# Smart_Restaurant.net
KiCad netlist of a schematic drawn in Altium Designer
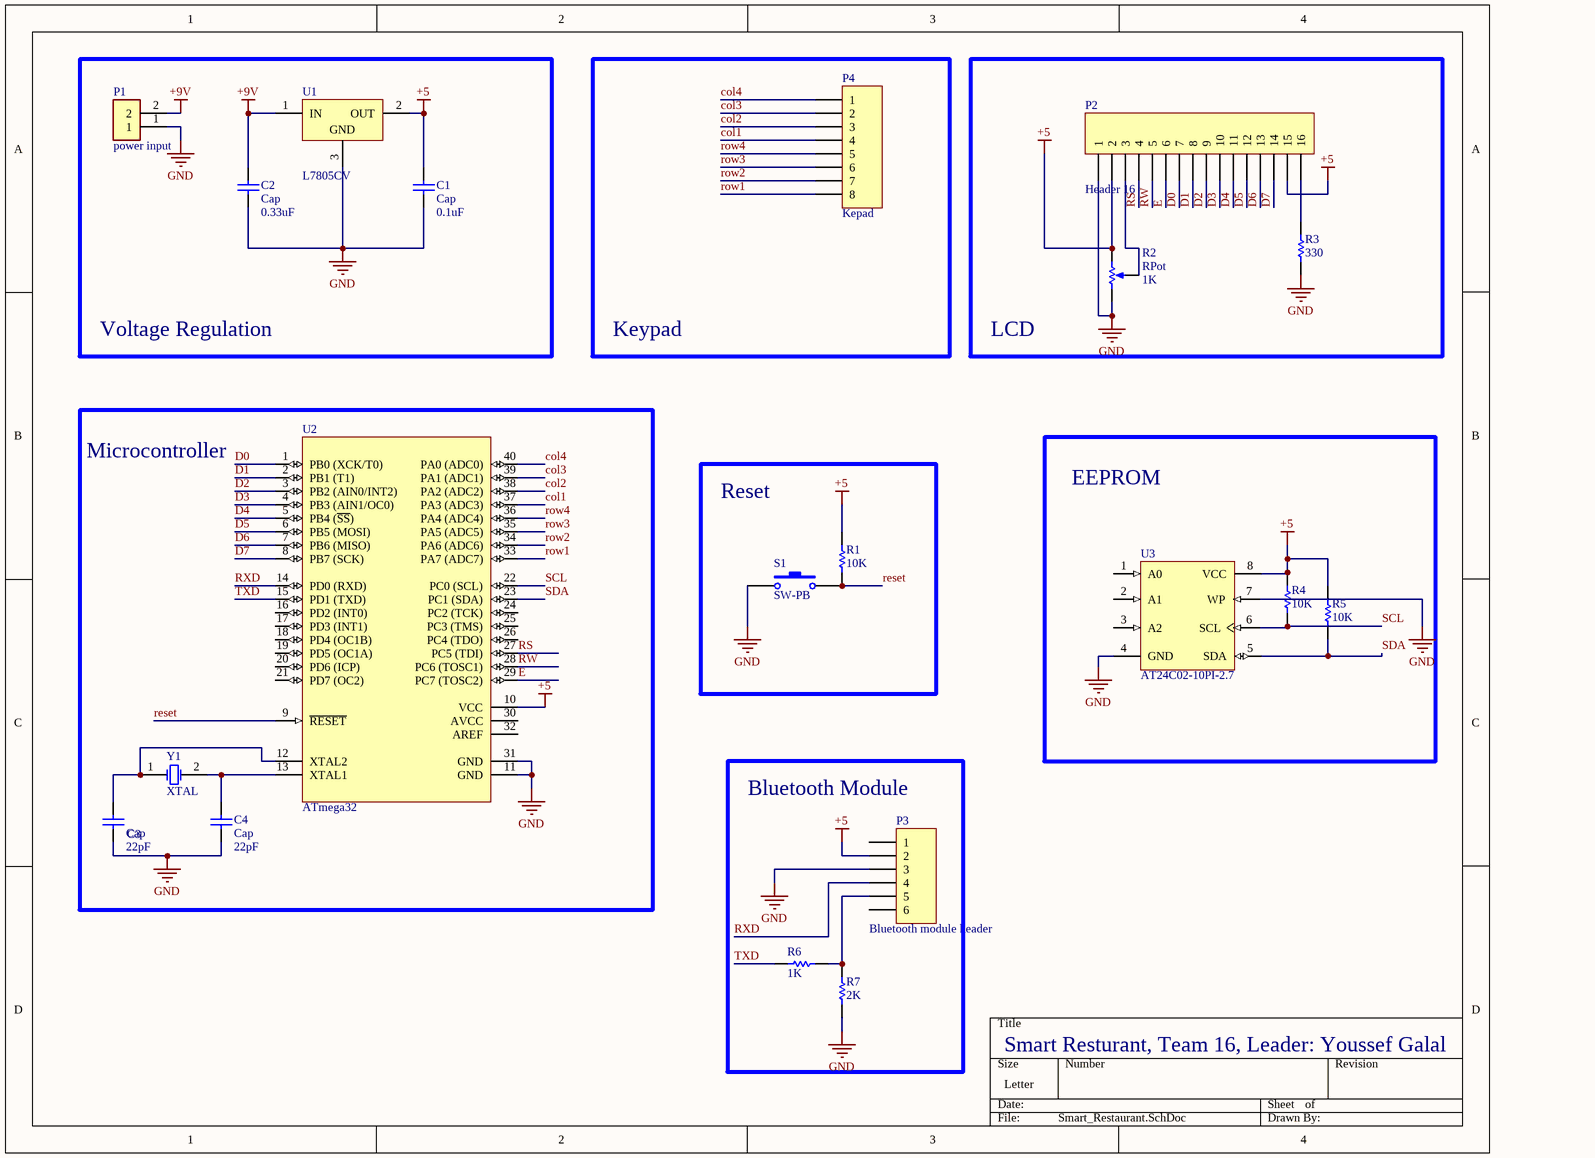
[diagram p0: Smart_Restaurant.SchDoc]

(export (version "E")
  (design (tool "Eeschema 10.0.6"))
  (components
    (comp (ref "C1")
      (value "Cap")
      (footprint "Miscellaneous Devices:CAPACITOR")
      (description "Capacitor")
      (fields (field (name "ALTIUM_VALUE") "0.1uF") (field (name "PUBLISHER") "Altium Limited"))
      (libsource (lib "Miscellaneous Devices") (part "Cap"))
    )
    (comp (ref "C2")
      (value "Cap")
      (footprint "Miscellaneous Devices:CAPACITOR")
      (description "Capacitor")
      (fields (field (name "ALTIUM_VALUE") "0.33uF") (field (name "PUBLISHER") "Altium Limited"))
      (libsource (lib "Miscellaneous Devices") (part "Cap"))
    )
    (comp (ref "C3")
      (value "Cap")
      (footprint "Miscellaneous Devices:CAPACITOR")
      (description "Capacitor")
      (fields (field (name "ALTIUM_VALUE") "22pF") (field (name "PUBLISHER") "Altium Limited"))
      (libsource (lib "Miscellaneous Devices") (part "Cap"))
    )
    (comp (ref "C4")
      (value "Cap")
      (footprint "Miscellaneous Devices:CAPACITOR")
      (description "Capacitor")
      (fields (field (name "ALTIUM_VALUE") "22pF") (field (name "PUBLISHER") "Altium Limited"))
      (libsource (lib "Miscellaneous Devices") (part "Cap"))
    )
    (comp (ref "P1")
      (value "power input")
      (footprint "TE_282837-2")
      (description "Connector Terminal Blocks Receptacle 2 Position 5.08mm Solder Straight Thru-Hole 13.5A/Contact")
      (fields (field (name "MF") "TE Connectivity") (field (name "MP") "282837-2"))
      (libsource (lib "Terminal_Block_2pins") (part "282837-2"))
    )
    (comp (ref "P2")
      (value "Header 16")
      (footprint "HDR1X16")
      (description "Header, 16-Pin")
      (fields (field (name "PUBLISHER") "Altium Limited"))
      (libsource (lib "Miscellaneous Connectors") (part "Header 16"))
    )
    (comp (ref "P3")
      (value "Bluetooth module header")
      (footprint "HDR1X6H")
      (description "Header, 6-Pin, Right Angle")
      (fields (field (name "PUBLISHER") "Altium Limited"))
      (libsource (lib "Miscellaneous Connectors") (part "Header 6H"))
    )
    (comp (ref "P4")
      (value "Kepad")
      (footprint "HDR1X8")
      (description "Header, 8-Pin")
      (fields (field (name "PUBLISHER") "Altium Limited"))
      (libsource (lib "Miscellaneous Connectors") (part "Header 8"))
    )
    (comp (ref "R1")
      (value "10K")
      (footprint "RO3.2x1.7")
      (description "Metal Film Resistor, 2 Ohm to 1M Ohm Range, 0.5% and 1% Tolerance, 0.25 W")
      (fields (field (name "PUBLISHER") "Altium Limited"))
      (libsource (lib "Panasonic Resistor") (part "EROS2C"))
    )
    (comp (ref "R2")
      (value "RPot")
      (footprint "VR5")
      (description "Potentiometer")
      (fields (field (name "ALTIUM_VALUE") "1K") (field (name "PUBLISHER") "Altium Limited"))
      (libsource (lib "Miscellaneous Devices") (part "RPot"))
    )
    (comp (ref "R3")
      (value "330")
      (footprint "RO3.2x1.7")
      (description "Metal Film Resistor, 2 Ohm to 1M Ohm Range, 0.5% and 1% Tolerance, 0.25 W")
      (fields (field (name "PUBLISHER") "Altium Limited"))
      (libsource (lib "Panasonic Resistor") (part "EROS2C"))
    )
    (comp (ref "R4")
      (value "10K")
      (footprint "RO3.2x1.7")
      (description "Metal Film Resistor, 2 Ohm to 1M Ohm Range, 0.5% and 1% Tolerance, 0.25 W")
      (fields (field (name "PUBLISHER") "Altium Limited"))
      (libsource (lib "Panasonic Resistor") (part "EROS2C"))
    )
    (comp (ref "R5")
      (value "10K")
      (footprint "RO3.2x1.7")
      (description "Metal Film Resistor, 2 Ohm to 1M Ohm Range, 0.5% and 1% Tolerance, 0.25 W")
      (fields (field (name "PUBLISHER") "Altium Limited"))
      (libsource (lib "Panasonic Resistor") (part "EROS2C"))
    )
    (comp (ref "R6")
      (value "1K")
      (footprint "RO3.2x1.7")
      (description "Metal Film Resistor, 2 Ohm to 1M Ohm Range, 0.5% and 1% Tolerance, 0.25 W")
      (fields (field (name "PUBLISHER") "Altium Limited"))
      (libsource (lib "Panasonic Resistor") (part "EROS2C"))
    )
    (comp (ref "R7")
      (value "2K")
      (footprint "RO3.2x1.7")
      (description "Metal Film Resistor, 2 Ohm to 1M Ohm Range, 0.5% and 1% Tolerance, 0.25 W")
      (fields (field (name "PUBLISHER") "Altium Limited"))
      (libsource (lib "Panasonic Resistor") (part "EROS2C"))
    )
    (comp (ref "S1")
      (value "SW-PB")
      (footprint "SPST-2")
      (description "Switch")
      (fields (field (name "PUBLISHER") "Altium Limited"))
      (libsource (lib "Miscellaneous Devices") (part "SW-PB"))
    )
    (comp (ref "U1")
      (value "L7805CV")
      (footprint "TO220ABN")
      (description "Positive Voltage Regulator")
      (fields (field (name "PUBLISHER") "Altium Limited"))
      (libsource (lib "ST Power Mgt Voltage Regulator") (part "L7805CV"))
    )
    (comp (ref "U2")
      (value "ATmega32")
      (footprint "40P6")
      (description "8-Bit AVR Microcontroller with 16K Bytes of In-System Programmable Flash Memory")
      (fields (field (name "PUBLISHER") "Altium Limited"))
      (libsource (lib "Atmel Microcontroller 8-Bit AVR") (part "ATmega16L-8PI"))
    )
    (comp (ref "U3")
      (value "AT24C02-10PI-2.7")
      (footprint "8P3")
      (description "2-WIre Serial EEPROM-2K-Dip-Industerial -Vcc=2.7to5.5V")
      (fields (field (name "MANUFACTURER") "Atmel"))
      (libsource (lib "Atmel EEPROM") (part "AT24C02-10PI-2.7"))
    )
    (comp (ref "Y1")
      (value "XTAL")
      (footprint "Miscellaneous Devices:XTAL")
      (description "Crystal Oscillator")
      (fields (field (name "PUBLISHER") "Altium Limited"))
      (libsource (lib "Miscellaneous Devices") (part "XTAL"))
    )
  )
  (nets
    (net (code "1") (name "+5") (class "Default")
      (node (ref "C1") (pin "2") (pinfunction "2_2") (pintype "passive"))
      (node (ref "P2") (pin "15") (pinfunction "15_15") (pintype "passive"))
      (node (ref "P2") (pin "2") (pinfunction "2_2") (pintype "passive"))
      (node (ref "P3") (pin "2") (pinfunction "2_2") (pintype "passive"))
      (node (ref "R1") (pin "2") (pinfunction "2_2") (pintype "passive"))
      (node (ref "R2") (pin "3") (pinfunction "BOT_3") (pintype "passive"))
      (node (ref "R4") (pin "2") (pinfunction "2_2") (pintype "passive"))
      (node (ref "R5") (pin "2") (pinfunction "2_2") (pintype "passive"))
      (node (ref "U1") (pin "2") (pinfunction "OUT_2") (pintype "power_in"))
      (node (ref "U2") (pin "10") (pinfunction "VCC_10") (pintype "power_in"))
      (node (ref "U3") (pin "8") (pinfunction "VCC_8") (pintype "power_in"))
    )
    (net (code "2") (name "+9V") (class "Default")
      (node (ref "C2") (pin "2") (pinfunction "2_2") (pintype "passive"))
      (node (ref "P1") (pin "2") (pinfunction "2_2") (pintype "passive"))
      (node (ref "U1") (pin "1") (pinfunction "IN_1") (pintype "power_in"))
    )
    (net (code "3") (name "/D0") (class "Default")
      (node (ref "P2") (pin "7") (pinfunction "7_7") (pintype "passive"))
      (node (ref "U2") (pin "1") (pinfunction "PB0_(XCK/T0)_1") (pintype "bidirectional"))
    )
    (net (code "4") (name "/D1") (class "Default")
      (node (ref "P2") (pin "8") (pinfunction "8_8") (pintype "passive"))
      (node (ref "U2") (pin "2") (pinfunction "PB1_(T1)_2") (pintype "bidirectional"))
    )
    (net (code "5") (name "/D2") (class "Default")
      (node (ref "P2") (pin "9") (pinfunction "9_9") (pintype "passive"))
      (node (ref "U2") (pin "3") (pinfunction "PB2_(AIN0/INT2)_3") (pintype "bidirectional"))
    )
    (net (code "6") (name "/D3") (class "Default")
      (node (ref "P2") (pin "10") (pinfunction "10_10") (pintype "passive"))
      (node (ref "U2") (pin "4") (pinfunction "PB3_(AIN1/OC0)_4") (pintype "bidirectional"))
    )
    (net (code "7") (name "/D4") (class "Default")
      (node (ref "P2") (pin "11") (pinfunction "11_11") (pintype "passive"))
      (node (ref "U2") (pin "5") (pinfunction "PB4_(~{SS})_5") (pintype "bidirectional"))
    )
    (net (code "8") (name "/D5") (class "Default")
      (node (ref "P2") (pin "12") (pinfunction "12_12") (pintype "passive"))
      (node (ref "U2") (pin "6") (pinfunction "PB5_(MOSI)_6") (pintype "bidirectional"))
    )
    (net (code "9") (name "/D6") (class "Default")
      (node (ref "P2") (pin "13") (pinfunction "13_13") (pintype "passive"))
      (node (ref "U2") (pin "7") (pinfunction "PB6_(MISO)_7") (pintype "bidirectional"))
    )
    (net (code "10") (name "/D7") (class "Default")
      (node (ref "P2") (pin "14") (pinfunction "14_14") (pintype "passive"))
      (node (ref "U2") (pin "8") (pinfunction "PB7_(SCK)_8") (pintype "bidirectional"))
    )
    (net (code "11") (name "/E") (class "Default")
      (node (ref "P2") (pin "6") (pinfunction "6_6") (pintype "passive"))
      (node (ref "U2") (pin "29") (pinfunction "PC7_(TOSC2)_29") (pintype "bidirectional"))
    )
    (net (code "12") (name "/RS") (class "Default")
      (node (ref "P2") (pin "4") (pinfunction "4_4") (pintype "passive"))
      (node (ref "U2") (pin "27") (pinfunction "PC5_(TDI)_27") (pintype "bidirectional"))
    )
    (net (code "13") (name "/RW") (class "Default")
      (node (ref "P2") (pin "5") (pinfunction "5_5") (pintype "passive"))
      (node (ref "U2") (pin "28") (pinfunction "PC6_(TOSC1)_28") (pintype "bidirectional"))
    )
    (net (code "14") (name "/RXD") (class "Default")
      (node (ref "P3") (pin "4") (pinfunction "4_4") (pintype "passive"))
      (node (ref "U2") (pin "14") (pinfunction "PD0_(RXD)_14") (pintype "bidirectional"))
    )
    (net (code "15") (name "/SCL") (class "Default")
      (node (ref "R4") (pin "1") (pinfunction "1_1") (pintype "passive"))
      (node (ref "U2") (pin "22") (pinfunction "PC0_(SCL)_22") (pintype "bidirectional"))
      (node (ref "U3") (pin "6") (pinfunction "SCL_6") (pintype "input"))
    )
    (net (code "16") (name "/SDA") (class "Default")
      (node (ref "R5") (pin "1") (pinfunction "1_1") (pintype "passive"))
      (node (ref "U2") (pin "23") (pinfunction "PC1_(SDA)_23") (pintype "bidirectional"))
      (node (ref "U3") (pin "5") (pinfunction "SDA_5") (pintype "bidirectional"))
    )
    (net (code "17") (name "/TXD") (class "Default")
      (node (ref "R6") (pin "2") (pinfunction "2_2") (pintype "passive"))
      (node (ref "U2") (pin "15") (pinfunction "PD1_(TXD)_15") (pintype "bidirectional"))
    )
    (net (code "18") (name "/col1") (class "Default")
      (node (ref "P4") (pin "4") (pinfunction "4_4") (pintype "passive"))
      (node (ref "U2") (pin "37") (pinfunction "PA3_(ADC3)_37") (pintype "bidirectional"))
    )
    (net (code "19") (name "/col2") (class "Default")
      (node (ref "P4") (pin "3") (pinfunction "3_3") (pintype "passive"))
      (node (ref "U2") (pin "38") (pinfunction "PA2_(ADC2)_38") (pintype "bidirectional"))
    )
    (net (code "20") (name "/col3") (class "Default")
      (node (ref "P4") (pin "2") (pinfunction "2_2") (pintype "passive"))
      (node (ref "U2") (pin "39") (pinfunction "PA1_(ADC1)_39") (pintype "bidirectional"))
    )
    (net (code "21") (name "/col4") (class "Default")
      (node (ref "P4") (pin "1") (pinfunction "1_1") (pintype "passive"))
      (node (ref "U2") (pin "40") (pinfunction "PA0_(ADC0)_40") (pintype "bidirectional"))
    )
    (net (code "22") (name "/reset") (class "Default")
      (node (ref "R1") (pin "1") (pinfunction "1_1") (pintype "passive"))
      (node (ref "S1") (pin "2") (pinfunction "2_2") (pintype "passive"))
      (node (ref "U2") (pin "9") (pinfunction "~{RESET}_9") (pintype "input"))
    )
    (net (code "23") (name "/row1") (class "Default")
      (node (ref "P4") (pin "8") (pinfunction "8_8") (pintype "passive"))
      (node (ref "U2") (pin "33") (pinfunction "PA7_(ADC7)_33") (pintype "bidirectional"))
    )
    (net (code "24") (name "/row2") (class "Default")
      (node (ref "P4") (pin "7") (pinfunction "7_7") (pintype "passive"))
      (node (ref "U2") (pin "34") (pinfunction "PA6_(ADC6)_34") (pintype "bidirectional"))
    )
    (net (code "25") (name "/row3") (class "Default")
      (node (ref "P4") (pin "6") (pinfunction "6_6") (pintype "passive"))
      (node (ref "U2") (pin "35") (pinfunction "PA5_(ADC5)_35") (pintype "bidirectional"))
    )
    (net (code "26") (name "/row4") (class "Default")
      (node (ref "P4") (pin "5") (pinfunction "5_5") (pintype "passive"))
      (node (ref "U2") (pin "36") (pinfunction "PA4_(ADC4)_36") (pintype "bidirectional"))
    )
    (net (code "27") (name "GND") (class "Default")
      (node (ref "C1") (pin "1") (pinfunction "1_1") (pintype "passive"))
      (node (ref "C2") (pin "1") (pinfunction "1_1") (pintype "passive"))
      (node (ref "C3") (pin "1") (pinfunction "1_1") (pintype "passive"))
      (node (ref "C4") (pin "1") (pinfunction "1_1") (pintype "passive"))
      (node (ref "P1") (pin "1") (pinfunction "1_1") (pintype "passive"))
      (node (ref "P2") (pin "1") (pinfunction "1_1") (pintype "passive"))
      (node (ref "P3") (pin "3") (pinfunction "3_3") (pintype "passive"))
      (node (ref "R2") (pin "1") (pinfunction "TOP_1") (pintype "passive"))
      (node (ref "R3") (pin "1") (pinfunction "1_1") (pintype "passive"))
      (node (ref "R7") (pin "2") (pinfunction "2_2") (pintype "passive"))
      (node (ref "S1") (pin "1") (pinfunction "1_1") (pintype "passive"))
      (node (ref "U1") (pin "3") (pinfunction "GND_3") (pintype "power_in"))
      (node (ref "U2") (pin "11") (pinfunction "GND_11") (pintype "power_in"))
      (node (ref "U2") (pin "31") (pinfunction "GND_31") (pintype "power_in"))
      (node (ref "U3") (pin "4") (pinfunction "GND_4") (pintype "power_in"))
      (node (ref "U3") (pin "7") (pinfunction "WP_7") (pintype "input"))
    )
    (net (code "28") (name "Net-(P2-Pad16)") (class "Default")
      (node (ref "P2") (pin "16") (pinfunction "16_16") (pintype "passive"))
      (node (ref "R3") (pin "2") (pinfunction "2_2") (pintype "passive"))
    )
    (net (code "29") (name "Net-(P3-Pad5)") (class "Default")
      (node (ref "P3") (pin "5") (pinfunction "5_5") (pintype "passive"))
      (node (ref "R6") (pin "1") (pinfunction "1_1") (pintype "passive"))
      (node (ref "R7") (pin "1") (pinfunction "1_1") (pintype "passive"))
    )
    (net (code "30") (name "Net-(R2-TAP)") (class "Default")
      (node (ref "P2") (pin "3") (pinfunction "3_3") (pintype "passive"))
      (node (ref "R2") (pin "2") (pinfunction "TAP_2") (pintype "passive"))
    )
    (net (code "31") (name "Net-(U2-XTAL1)") (class "Default")
      (node (ref "C4") (pin "2") (pinfunction "2_2") (pintype "passive"))
      (node (ref "U2") (pin "13") (pinfunction "XTAL1_13") (pintype "passive"))
      (node (ref "Y1") (pin "2") (pinfunction "OSC2_2") (pintype "passive"))
    )
    (net (code "32") (name "Net-(U2-XTAL2)") (class "Default")
      (node (ref "C3") (pin "2") (pinfunction "2_2") (pintype "passive"))
      (node (ref "U2") (pin "12") (pinfunction "XTAL2_12") (pintype "passive"))
      (node (ref "Y1") (pin "1") (pinfunction "OSC1_1") (pintype "passive"))
    )
    (net (code "33") (name "unconnected-(P3-Pad1)") (class "Default")
      (node (ref "P3") (pin "1") (pinfunction "1_1") (pintype "passive"))
    )
    (net (code "34") (name "unconnected-(P3-Pad6)") (class "Default")
      (node (ref "P3") (pin "6") (pinfunction "6_6") (pintype "passive"))
    )
    (net (code "35") (name "unconnected-(U2-AREF-Pad32)") (class "Default")
      (node (ref "U2") (pin "32") (pinfunction "AREF_32") (pintype "passive"))
    )
    (net (code "36") (name "unconnected-(U2-AVCC-Pad30)") (class "Default")
      (node (ref "U2") (pin "30") (pinfunction "AVCC_30") (pintype "power_in"))
    )
    (net (code "37") (name "unconnected-(U2-PC2_(TCK)-Pad24)") (class "Default")
      (node (ref "U2") (pin "24") (pinfunction "PC2_(TCK)_24") (pintype "bidirectional"))
    )
    (net (code "38") (name "unconnected-(U2-PC3_(TMS)-Pad25)") (class "Default")
      (node (ref "U2") (pin "25") (pinfunction "PC3_(TMS)_25") (pintype "bidirectional"))
    )
    (net (code "39") (name "unconnected-(U2-PC4_(TDO)-Pad26)") (class "Default")
      (node (ref "U2") (pin "26") (pinfunction "PC4_(TDO)_26") (pintype "bidirectional"))
    )
    (net (code "40") (name "unconnected-(U2-PD2_(INT0)-Pad16)") (class "Default")
      (node (ref "U2") (pin "16") (pinfunction "PD2_(INT0)_16") (pintype "bidirectional"))
    )
    (net (code "41") (name "unconnected-(U2-PD3_(INT1)-Pad17)") (class "Default")
      (node (ref "U2") (pin "17") (pinfunction "PD3_(INT1)_17") (pintype "bidirectional"))
    )
    (net (code "42") (name "unconnected-(U2-PD4_(OC1B)-Pad18)") (class "Default")
      (node (ref "U2") (pin "18") (pinfunction "PD4_(OC1B)_18") (pintype "bidirectional"))
    )
    (net (code "43") (name "unconnected-(U2-PD5_(OC1A)-Pad19)") (class "Default")
      (node (ref "U2") (pin "19") (pinfunction "PD5_(OC1A)_19") (pintype "bidirectional"))
    )
    (net (code "44") (name "unconnected-(U2-PD6_(ICP)-Pad20)") (class "Default")
      (node (ref "U2") (pin "20") (pinfunction "PD6_(ICP)_20") (pintype "bidirectional"))
    )
    (net (code "45") (name "unconnected-(U2-PD7_(OC2)-Pad21)") (class "Default")
      (node (ref "U2") (pin "21") (pinfunction "PD7_(OC2)_21") (pintype "bidirectional"))
    )
    (net (code "46") (name "unconnected-(U3-A0-Pad1)") (class "Default")
      (node (ref "U3") (pin "1") (pinfunction "A0_1") (pintype "input"))
    )
    (net (code "47") (name "unconnected-(U3-A1-Pad2)") (class "Default")
      (node (ref "U3") (pin "2") (pinfunction "A1_2") (pintype "input"))
    )
    (net (code "48") (name "unconnected-(U3-A2-Pad3)") (class "Default")
      (node (ref "U3") (pin "3") (pinfunction "A2_3") (pintype "input"))
    )
  )
)
